# PCB_MOTEUR_V0_2b.net
KiCad netlist of a schematic drawn in EAGLE
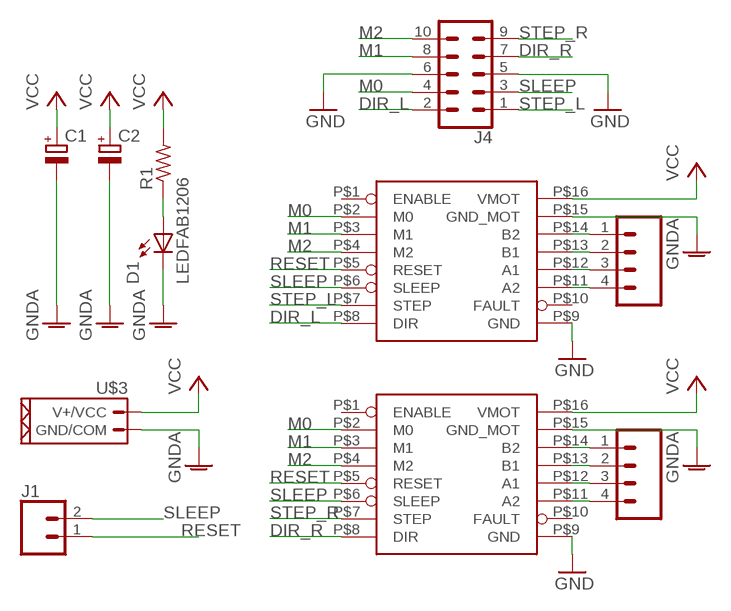
[diagram p0: schematic, sheet 1]

(export (version "E")
  (design (tool "Eeschema 10.0.6"))
  (components
    (comp (ref "C1")
      (value "CPOL-EUE3.5-8")
      (footprint "eagle-import:E3,5-8")
      (libsource (lib "eagle-import") (part "CPOL-EUE3.5-8"))
    )
    (comp (ref "C2")
      (value "CPOL-EUE3.5-8")
      (footprint "eagle-import:E3,5-8")
      (libsource (lib "eagle-import") (part "CPOL-EUE3.5-8"))
    )
    (comp (ref "D1")
      (value "LEDFAB1206")
      (footprint "eagle-import:LED1206FAB")
      (libsource (lib "eagle-import") (part "LEDFAB1206"))
    )
    (comp (ref "J1")
      (value "CONN_02")
      (footprint "eagle-import:1X02")
      (libsource (lib "eagle-import") (part "CONN_02"))
    )
    (comp (ref "J3")
      (value "CONN_04POLAR")
      (footprint "eagle-import:MOLEX-1X4")
      (libsource (lib "eagle-import") (part "CONN_04POLAR"))
    )
    (comp (ref "J4")
      (value "CONN_05X2SHD")
      (footprint "eagle-import:2X5-SHROUDED")
      (libsource (lib "eagle-import") (part "CONN_05X2SHD"))
    )
    (comp (ref "J5")
      (value "CONN_04POLAR")
      (footprint "eagle-import:MOLEX-1X4")
      (libsource (lib "eagle-import") (part "CONN_04POLAR"))
    )
    (comp (ref "R1")
      (value "RES-US1206FAB")
      (footprint "eagle-import:R1206FAB")
      (libsource (lib "eagle-import") (part "RES-US1206FAB"))
    )
    (comp (ref "U$1")
      (value "DRV8825")
      (footprint "eagle-import:DRIVER_CARRIER_POLOLU_16")
      (libsource (lib "eagle-import") (part "DRV8825"))
    )
    (comp (ref "U$2")
      (value "DRV8825")
      (footprint "eagle-import:DRIVER_CARRIER_POLOLU_16")
      (libsource (lib "eagle-import") (part "DRV8825"))
    )
    (comp (ref "U$3")
      (value "CONN_02_PUIXT30")
      (footprint "eagle-import:XT30_FEMALE")
      (libsource (lib "eagle-import") (part "CONN_02_PUIXT30"))
    )
  )
  (nets
    (net (code "1") (name "/DIR_L") (class "Default")
      (node (ref "J4") (pin "2") (pinfunction "2_2") (pintype "passive"))
      (node (ref "U$1") (pin "P$8") (pinfunction "DIR_P$8") (pintype "bidirectional"))
    )
    (net (code "2") (name "/DIR_R") (class "Default")
      (node (ref "J4") (pin "7") (pinfunction "7_7") (pintype "passive"))
      (node (ref "U$2") (pin "P$8") (pinfunction "DIR_P$8") (pintype "bidirectional"))
    )
    (net (code "3") (name "/M0") (class "Default")
      (node (ref "J4") (pin "4") (pinfunction "4_4") (pintype "passive"))
      (node (ref "U$1") (pin "P$2") (pinfunction "M0_P$2") (pintype "bidirectional"))
      (node (ref "U$2") (pin "P$2") (pinfunction "M0_P$2") (pintype "bidirectional"))
    )
    (net (code "4") (name "/M1") (class "Default")
      (node (ref "J4") (pin "8") (pinfunction "8_8") (pintype "passive"))
      (node (ref "U$1") (pin "P$3") (pinfunction "M1_P$3") (pintype "bidirectional"))
      (node (ref "U$2") (pin "P$3") (pinfunction "M1_P$3") (pintype "bidirectional"))
    )
    (net (code "5") (name "/M2") (class "Default")
      (node (ref "J4") (pin "10") (pinfunction "10_10") (pintype "passive"))
      (node (ref "U$1") (pin "P$4") (pinfunction "M2_P$4") (pintype "bidirectional"))
      (node (ref "U$2") (pin "P$4") (pinfunction "M2_P$4") (pintype "bidirectional"))
    )
    (net (code "6") (name "/RESET") (class "Default")
      (node (ref "J1") (pin "1") (pinfunction "1_1") (pintype "passive"))
      (node (ref "U$1") (pin "P$5") (pinfunction "RESET_P$5") (pintype "bidirectional"))
      (node (ref "U$2") (pin "P$5") (pinfunction "RESET_P$5") (pintype "bidirectional"))
    )
    (net (code "7") (name "/SLEEP") (class "Default")
      (node (ref "J1") (pin "2") (pinfunction "2_2") (pintype "passive"))
      (node (ref "J4") (pin "3") (pinfunction "3_3") (pintype "passive"))
      (node (ref "U$1") (pin "P$6") (pinfunction "SLEEP_P$6") (pintype "bidirectional"))
      (node (ref "U$2") (pin "P$6") (pinfunction "SLEEP_P$6") (pintype "bidirectional"))
    )
    (net (code "8") (name "/STEP_L") (class "Default")
      (node (ref "J4") (pin "1") (pinfunction "1_1") (pintype "passive"))
      (node (ref "U$1") (pin "P$7") (pinfunction "STEP_P$7") (pintype "bidirectional"))
    )
    (net (code "9") (name "/STEP_R") (class "Default")
      (node (ref "J4") (pin "9") (pinfunction "9_9") (pintype "passive"))
      (node (ref "U$2") (pin "P$7") (pinfunction "STEP_P$7") (pintype "bidirectional"))
    )
    (net (code "10") (name "GND") (class "Default")
      (node (ref "J4") (pin "5") (pinfunction "5_5") (pintype "passive"))
      (node (ref "J4") (pin "6") (pinfunction "6_6") (pintype "passive"))
      (node (ref "U$1") (pin "P$9") (pinfunction "GND_P$9") (pintype "bidirectional"))
      (node (ref "U$2") (pin "P$9") (pinfunction "GND_P$9") (pintype "bidirectional"))
    )
    (net (code "11") (name "GNDA") (class "Default")
      (node (ref "C1") (pin "-") (pinfunction "-_-") (pintype "passive"))
      (node (ref "C2") (pin "-") (pinfunction "-_-") (pintype "passive"))
      (node (ref "D1") (pin "2") (pinfunction "C_2") (pintype "passive"))
      (node (ref "U$1") (pin "P$15") (pinfunction "GND_MOT_P$15") (pintype "bidirectional"))
      (node (ref "U$2") (pin "P$15") (pinfunction "GND_MOT_P$15") (pintype "bidirectional"))
      (node (ref "U$3") (pin "P$2") (pinfunction "GND/COM_P$2") (pintype "passive"))
    )
    (net (code "12") (name "Net-(D1-A)") (class "Default")
      (node (ref "D1") (pin "1") (pinfunction "A_1") (pintype "passive"))
      (node (ref "R1") (pin "1") (pinfunction "1_1") (pintype "passive"))
    )
    (net (code "13") (name "Net-(U$1-A1)") (class "Default")
      (node (ref "J3") (pin "3") (pinfunction "3_3") (pintype "passive"))
      (node (ref "U$1") (pin "P$12") (pinfunction "A1_P$12") (pintype "bidirectional"))
    )
    (net (code "14") (name "Net-(U$1-A2)") (class "Default")
      (node (ref "J3") (pin "4") (pinfunction "4_4") (pintype "passive"))
      (node (ref "U$1") (pin "P$11") (pinfunction "A2_P$11") (pintype "bidirectional"))
    )
    (net (code "15") (name "Net-(U$1-B1)") (class "Default")
      (node (ref "J3") (pin "2") (pinfunction "2_2") (pintype "passive"))
      (node (ref "U$1") (pin "P$13") (pinfunction "B1_P$13") (pintype "bidirectional"))
    )
    (net (code "16") (name "Net-(U$1-B2)") (class "Default")
      (node (ref "J3") (pin "1") (pinfunction "1_1") (pintype "passive"))
      (node (ref "U$1") (pin "P$14") (pinfunction "B2_P$14") (pintype "bidirectional"))
    )
    (net (code "17") (name "Net-(U$2-A1)") (class "Default")
      (node (ref "J5") (pin "3") (pinfunction "3_3") (pintype "passive"))
      (node (ref "U$2") (pin "P$12") (pinfunction "A1_P$12") (pintype "bidirectional"))
    )
    (net (code "18") (name "Net-(U$2-A2)") (class "Default")
      (node (ref "J5") (pin "4") (pinfunction "4_4") (pintype "passive"))
      (node (ref "U$2") (pin "P$11") (pinfunction "A2_P$11") (pintype "bidirectional"))
    )
    (net (code "19") (name "Net-(U$2-B1)") (class "Default")
      (node (ref "J5") (pin "2") (pinfunction "2_2") (pintype "passive"))
      (node (ref "U$2") (pin "P$13") (pinfunction "B1_P$13") (pintype "bidirectional"))
    )
    (net (code "20") (name "Net-(U$2-B2)") (class "Default")
      (node (ref "J5") (pin "1") (pinfunction "1_1") (pintype "passive"))
      (node (ref "U$2") (pin "P$14") (pinfunction "B2_P$14") (pintype "bidirectional"))
    )
    (net (code "21") (name "VCC") (class "Default")
      (node (ref "C1") (pin "+") (pinfunction "+_+") (pintype "passive"))
      (node (ref "C2") (pin "+") (pinfunction "+_+") (pintype "passive"))
      (node (ref "R1") (pin "2") (pinfunction "2_2") (pintype "passive"))
      (node (ref "U$1") (pin "P$16") (pinfunction "VMOT_P$16") (pintype "bidirectional"))
      (node (ref "U$2") (pin "P$16") (pinfunction "VMOT_P$16") (pintype "bidirectional"))
      (node (ref "U$3") (pin "P$1") (pinfunction "V+/VCC_P$1") (pintype "passive"))
    )
    (net (code "22") (name "unconnected-(U$1-ENABLE-PadP$1)") (class "Default")
      (node (ref "U$1") (pin "P$1") (pinfunction "ENABLE_P$1") (pintype "bidirectional"))
    )
    (net (code "23") (name "unconnected-(U$1-FAULT-PadP$10)") (class "Default")
      (node (ref "U$1") (pin "P$10") (pinfunction "FAULT_P$10") (pintype "bidirectional"))
    )
    (net (code "24") (name "unconnected-(U$2-ENABLE-PadP$1)") (class "Default")
      (node (ref "U$2") (pin "P$1") (pinfunction "ENABLE_P$1") (pintype "bidirectional"))
    )
    (net (code "25") (name "unconnected-(U$2-FAULT-PadP$10)") (class "Default")
      (node (ref "U$2") (pin "P$10") (pinfunction "FAULT_P$10") (pintype "bidirectional"))
    )
  )
)
